# SCH_USB-HUB_2026-07-22.net
KiCad netlist of a schematic drawn in EasyEDA
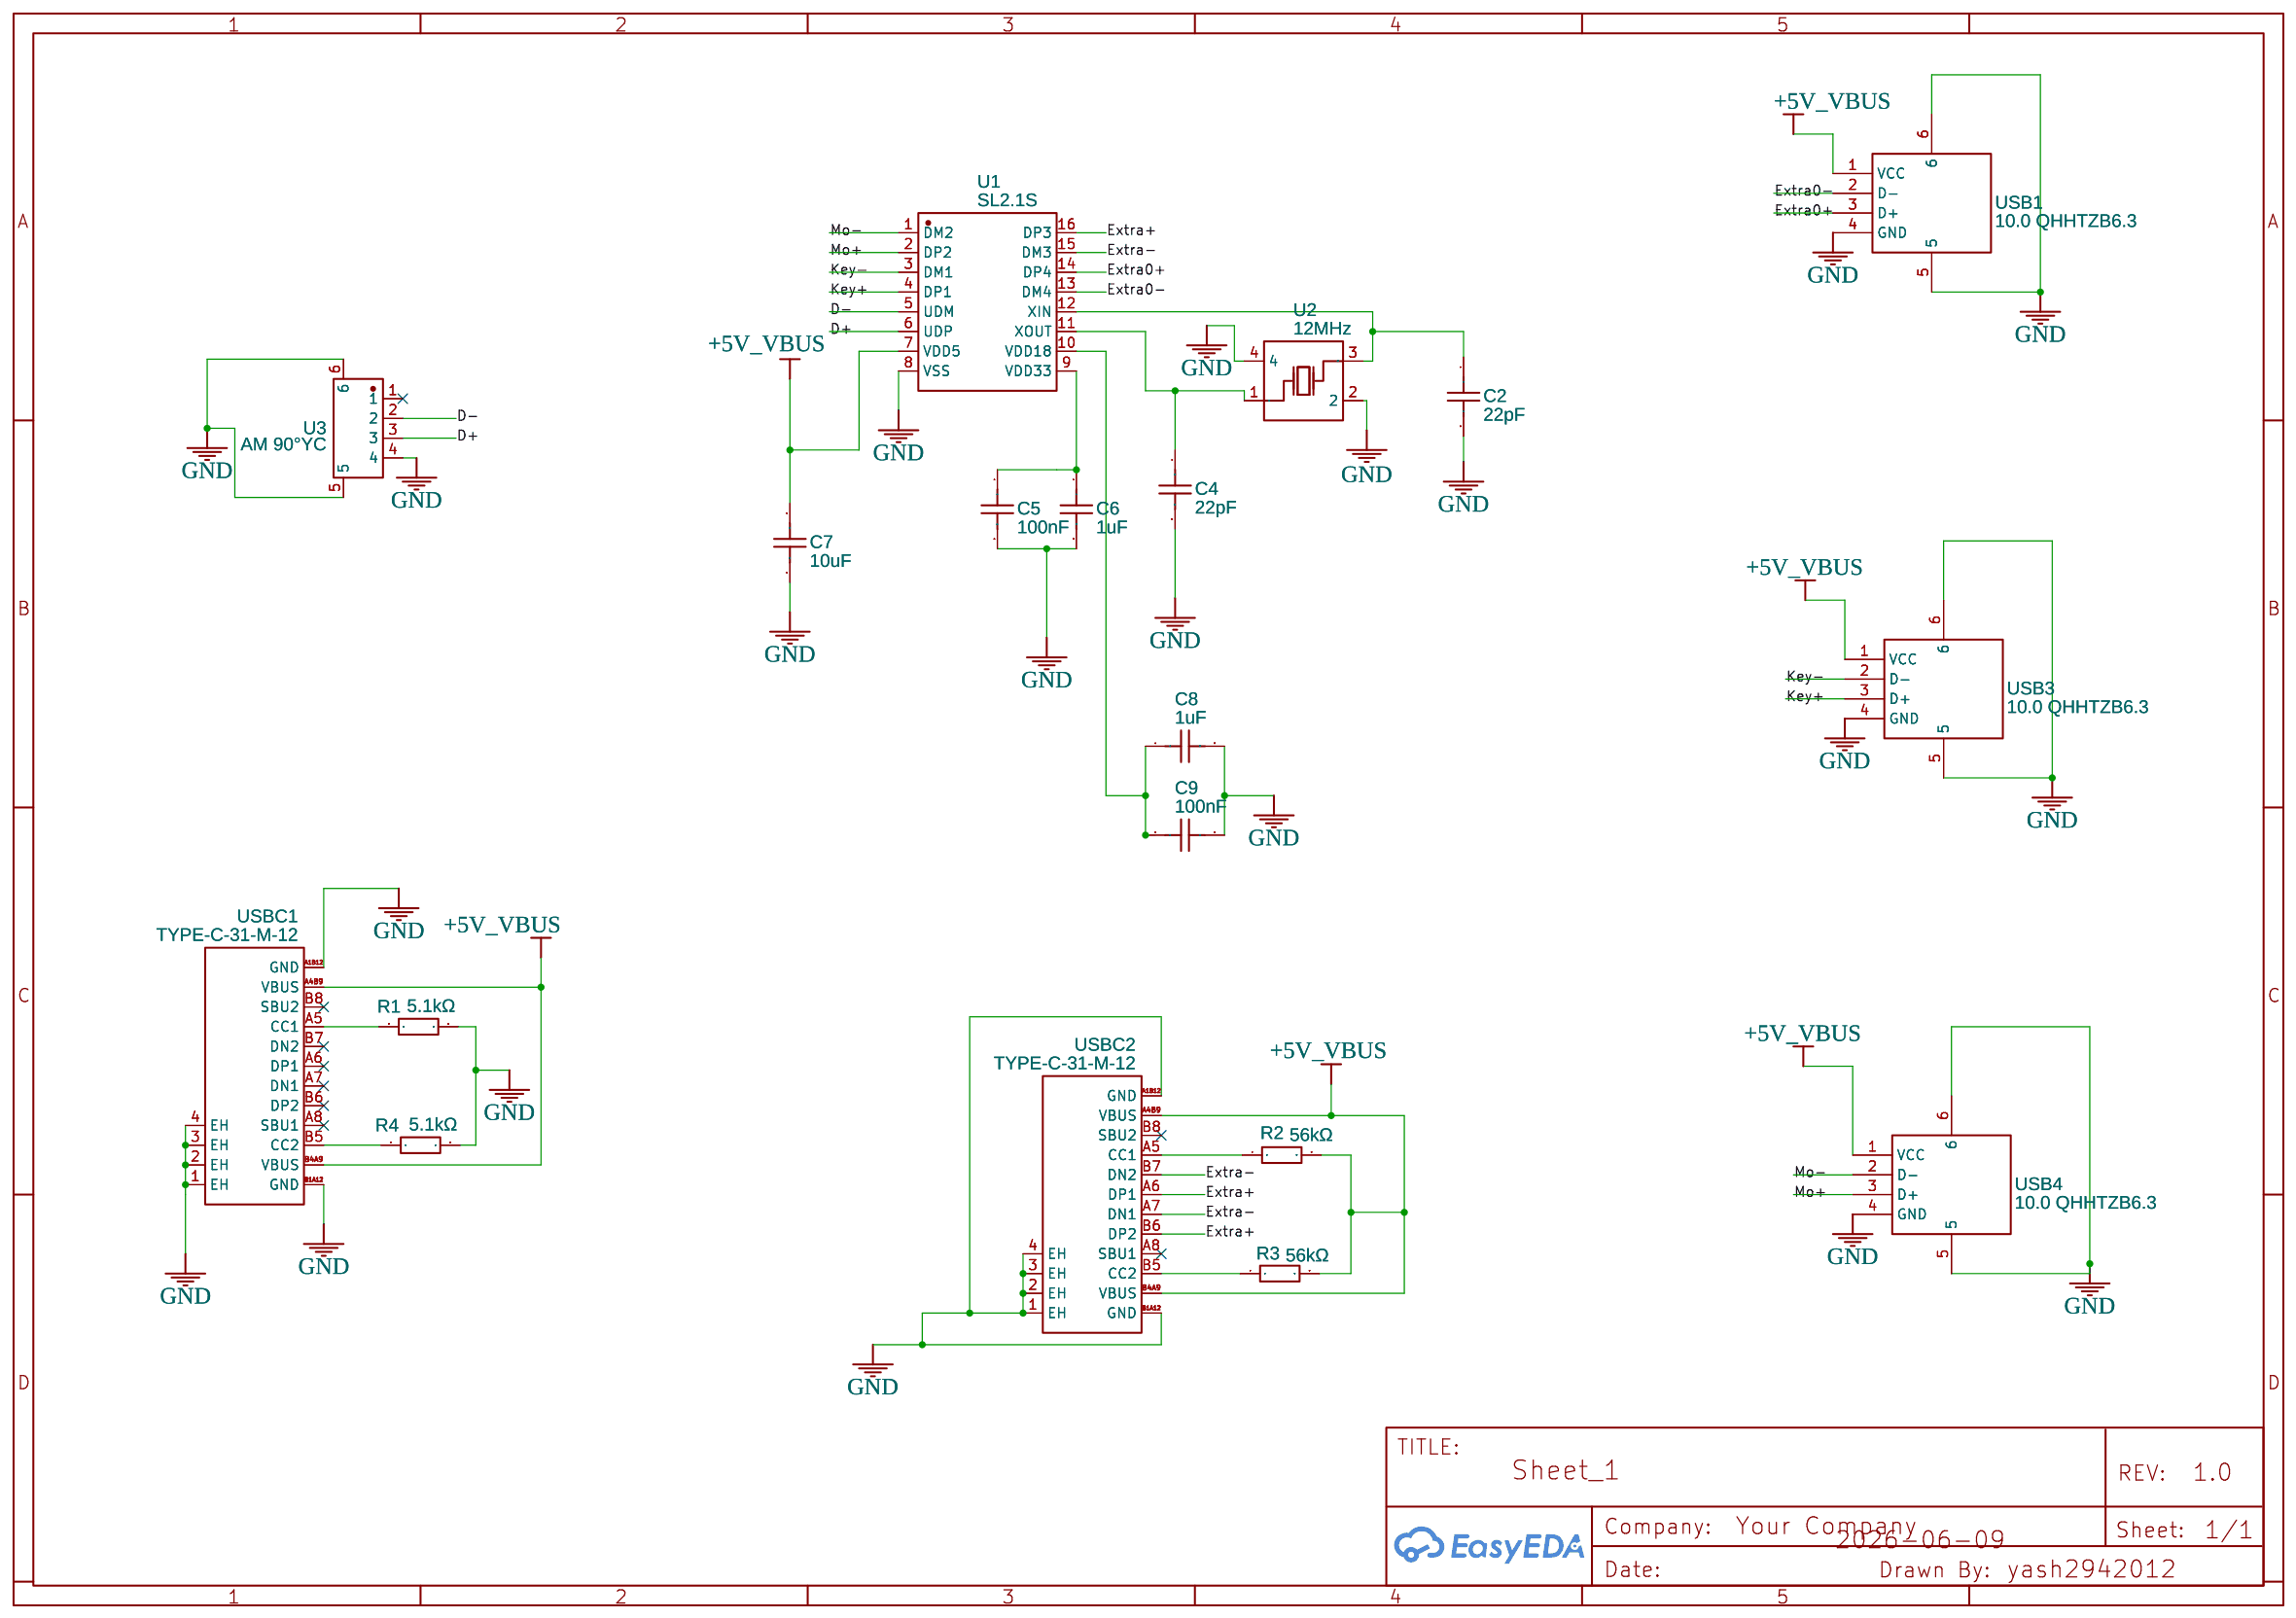
[diagram p0: schematic sheet]

(export (version "E")
  (design (tool "Eeschema 10.0.6"))
  (components
    (comp (ref "C2")
      (value "22pF")
      (fields
        (field (name "Manufacturer Part") "CC0603KRNPO9BN220")
        (field (name "Manufacturer") "YAGEO(国巨)")
      )
      (libsource (lib "") (part "CC0603KRNPO9BN220"))
    )
    (comp (ref "C4")
      (value "22pF")
      (fields
        (field (name "Manufacturer Part") "CC0603KRNPO9BN220")
        (field (name "Manufacturer") "YAGEO(国巨)")
      )
      (libsource (lib "") (part "CC0603KRNPO9BN220"))
    )
    (comp (ref "C5")
      (value "100nF")
      (fields
        (field (name "Manufacturer Part") "CL05B104KO5NNNC")
        (field (name "Manufacturer") "SAMSUNG(三星)")
      )
      (libsource (lib "") (part "CL05B104KO5NNNC"))
    )
    (comp (ref "C6")
      (value "1uF")
      (fields
        (field (name "Manufacturer Part") "CC0805KKX5R5BB105")
        (field (name "Manufacturer") "YAGEO(国巨)")
      )
      (libsource (lib "") (part "CC0805KKX5R5BB105_1"))
    )
    (comp (ref "C7")
      (value "10uF")
      (fields
        (field (name "Manufacturer Part") "CC0805KKX5R5BB106")
        (field (name "Manufacturer") "YAGEO(国巨)")
      )
      (libsource (lib "") (part "CC0805KKX5R5BB106"))
    )
    (comp (ref "C8")
      (value "1uF")
      (fields
        (field (name "Manufacturer Part") "CC0805KKX5R5BB105")
        (field (name "Manufacturer") "YAGEO(国巨)")
      )
      (libsource (lib "") (part "CC0805KKX5R5BB105"))
    )
    (comp (ref "C9")
      (value "100nF")
      (fields
        (field (name "Manufacturer Part") "CL05B104KO5NNNC")
        (field (name "Manufacturer") "SAMSUNG(三星)")
      )
      (libsource (lib "") (part "CL05B104KO5NNNC_1"))
    )
    (comp (ref "R1")
      (value "5.1kΩ")
      (fields
        (field (name "Manufacturer Part") "0402WGF5101TCE")
        (field (name "Manufacturer") "UNI-ROYAL(厚声)")
      )
      (libsource (lib "") (part "0402WGF5101TCE"))
    )
    (comp (ref "R2")
      (value "56kΩ")
      (fields
        (field (name "Manufacturer Part") "0402WGF5602TCE")
        (field (name "Manufacturer") "UNI-ROYAL(厚声)")
      )
      (libsource (lib "") (part "0402WGF5602TCE"))
    )
    (comp (ref "R3")
      (value "56kΩ")
      (fields
        (field (name "Manufacturer Part") "0402WGF5602TCE")
        (field (name "Manufacturer") "UNI-ROYAL(厚声)")
      )
      (libsource (lib "") (part "0402WGF5602TCE"))
    )
    (comp (ref "R4")
      (value "5.1kΩ")
      (fields
        (field (name "Manufacturer Part") "0402WGF5101TCE")
        (field (name "Manufacturer") "UNI-ROYAL(厚声)")
      )
      (libsource (lib "") (part "0402WGF5101TCE"))
    )
    (comp (ref "U1")
      (value "SL2.1S")
      (fields (field (name "Manufacturer Part") "SL2.1s") (field (name "Manufacturer") "CoreChips(和芯润德)"))
      (libsource (lib "") (part "SL2.1S"))
    )
    (comp (ref "U2")
      (value "12MHz")
      (fields
        (field (name "Manufacturer Part") "ABM10AIG-12.000MHZ-4Z-T3")
        (field (name "Manufacturer") "ABRACON")
      )
      (libsource (lib "") (part "ABM10AIG-12.000MHZ-4Z-T3"))
    )
    (comp (ref "U3")
      (value "AM 90°YC")
      (fields (field (name "Manufacturer Part") "AM 90 YC") (field (name "Manufacturer") "SHOU HAN(首韩)"))
      (libsource (lib "") (part "AM 90°YC"))
    )
    (comp (ref "USB1")
      (value "10.0 QHHTZB6.3")
      (fields (field (name "Manufacturer") "SHOU HAN(首韩)"))
      (libsource (lib "") (part "10.0 QHHTZB6.3"))
    )
    (comp (ref "USB3")
      (value "10.0 QHHTZB6.3")
      (fields (field (name "Manufacturer") "SHOU HAN(首韩)"))
      (libsource (lib "") (part "10.0 QHHTZB6.3"))
    )
    (comp (ref "USB4")
      (value "10.0 QHHTZB6.3")
      (fields (field (name "Manufacturer") "SHOU HAN(首韩)"))
      (libsource (lib "") (part "10.0 QHHTZB6.3"))
    )
    (comp (ref "USBC1")
      (value "TYPE-C-31-M-12")
      (fields (field (name "Manufacturer") "韩国韩荣"))
      (libsource (lib "") (part "TYPE-C-31-M-12"))
    )
    (comp (ref "USBC2")
      (value "TYPE-C-31-M-12")
      (fields (field (name "Manufacturer") "韩国韩荣"))
      (libsource (lib "") (part "TYPE-C-31-M-12"))
    )
  )
  (nets
    (net (code "1") (name "+5V_VBUS") (class "Default")
      (node (ref "C7") (pin "1") (pinfunction "1_1") (pintype "unspecified"))
      (node (ref "R2") (pin "2") (pinfunction "2_2") (pintype "input"))
      (node (ref "R3") (pin "2") (pinfunction "2_2") (pintype "input"))
      (node (ref "U1") (pin "7") (pinfunction "VDD5_7") (pintype "unspecified"))
      (node (ref "USB1") (pin "1") (pinfunction "VCC_1") (pintype "unspecified"))
      (node (ref "USB3") (pin "1") (pinfunction "VCC_1") (pintype "unspecified"))
      (node (ref "USB4") (pin "1") (pinfunction "VCC_1") (pintype "unspecified"))
      (node (ref "USBC1") (pin "A4B9") (pinfunction "VBUS_A4B9") (pintype "unspecified"))
      (node (ref "USBC1") (pin "B4A9") (pinfunction "VBUS_B4A9") (pintype "unspecified"))
      (node (ref "USBC2") (pin "A4B9") (pinfunction "VBUS_A4B9") (pintype "unspecified"))
      (node (ref "USBC2") (pin "B4A9") (pinfunction "VBUS_B4A9") (pintype "unspecified"))
    )
    (net (code "2") (name "/D+") (class "Default")
      (node (ref "U1") (pin "6") (pinfunction "UDP_6") (pintype "unspecified"))
      (node (ref "U3") (pin "3") (pinfunction "3_3") (pintype "unspecified"))
    )
    (net (code "3") (name "/D-") (class "Default")
      (node (ref "U1") (pin "5") (pinfunction "UDM_5") (pintype "unspecified"))
      (node (ref "U3") (pin "2") (pinfunction "2_2") (pintype "unspecified"))
    )
    (net (code "4") (name "/Extra+") (class "Default")
      (node (ref "U1") (pin "16") (pinfunction "DP3_16") (pintype "unspecified"))
      (node (ref "USBC2") (pin "A6") (pinfunction "DP1_A6") (pintype "unspecified"))
      (node (ref "USBC2") (pin "B6") (pinfunction "DP2_B6") (pintype "unspecified"))
    )
    (net (code "5") (name "/Extra-") (class "Default")
      (node (ref "U1") (pin "15") (pinfunction "DM3_15") (pintype "unspecified"))
      (node (ref "USBC2") (pin "A7") (pinfunction "DN1_A7") (pintype "unspecified"))
      (node (ref "USBC2") (pin "B7") (pinfunction "DN2_B7") (pintype "unspecified"))
    )
    (net (code "6") (name "/Extra0+") (class "Default")
      (node (ref "U1") (pin "14") (pinfunction "DP4_14") (pintype "unspecified"))
      (node (ref "USB1") (pin "3") (pinfunction "D+_3") (pintype "unspecified"))
    )
    (net (code "7") (name "/Extra0-") (class "Default")
      (node (ref "U1") (pin "13") (pinfunction "DM4_13") (pintype "unspecified"))
      (node (ref "USB1") (pin "2") (pinfunction "D-_2") (pintype "unspecified"))
    )
    (net (code "8") (name "/Key+") (class "Default")
      (node (ref "U1") (pin "4") (pinfunction "DP1_4") (pintype "unspecified"))
      (node (ref "USB3") (pin "3") (pinfunction "D+_3") (pintype "unspecified"))
    )
    (net (code "9") (name "/Key-") (class "Default")
      (node (ref "U1") (pin "3") (pinfunction "DM1_3") (pintype "unspecified"))
      (node (ref "USB3") (pin "2") (pinfunction "D-_2") (pintype "unspecified"))
    )
    (net (code "10") (name "/Mo+") (class "Default")
      (node (ref "U1") (pin "2") (pinfunction "DP2_2") (pintype "unspecified"))
      (node (ref "USB4") (pin "3") (pinfunction "D+_3") (pintype "unspecified"))
    )
    (net (code "11") (name "/Mo-") (class "Default")
      (node (ref "U1") (pin "1") (pinfunction "DM2_1") (pintype "unspecified"))
      (node (ref "USB4") (pin "2") (pinfunction "D-_2") (pintype "unspecified"))
    )
    (net (code "12") (name "GND") (class "Default")
      (node (ref "C2") (pin "2") (pinfunction "2_2") (pintype "unspecified"))
      (node (ref "C4") (pin "2") (pinfunction "2_2") (pintype "unspecified"))
      (node (ref "C5") (pin "2") (pinfunction "2_2") (pintype "unspecified"))
      (node (ref "C6") (pin "2") (pinfunction "2_2") (pintype "unspecified"))
      (node (ref "C7") (pin "2") (pinfunction "2_2") (pintype "unspecified"))
      (node (ref "C8") (pin "2") (pinfunction "2_2") (pintype "unspecified"))
      (node (ref "C9") (pin "2") (pinfunction "2_2") (pintype "unspecified"))
      (node (ref "R1") (pin "2") (pinfunction "2_2") (pintype "input"))
      (node (ref "R4") (pin "2") (pinfunction "2_2") (pintype "input"))
      (node (ref "U1") (pin "8") (pinfunction "VSS_8") (pintype "unspecified"))
      (node (ref "U2") (pin "2") (pinfunction "2_2") (pintype "unspecified"))
      (node (ref "U2") (pin "4") (pinfunction "4_4") (pintype "unspecified"))
      (node (ref "U3") (pin "4") (pinfunction "4_4") (pintype "unspecified"))
      (node (ref "U3") (pin "5") (pinfunction "5_5") (pintype "unspecified"))
      (node (ref "U3") (pin "6") (pinfunction "6_6") (pintype "unspecified"))
      (node (ref "USB1") (pin "4") (pinfunction "GND_4") (pintype "unspecified"))
      (node (ref "USB1") (pin "5") (pinfunction "5_5") (pintype "unspecified"))
      (node (ref "USB1") (pin "6") (pinfunction "6_6") (pintype "unspecified"))
      (node (ref "USB3") (pin "4") (pinfunction "GND_4") (pintype "unspecified"))
      (node (ref "USB3") (pin "5") (pinfunction "5_5") (pintype "unspecified"))
      (node (ref "USB3") (pin "6") (pinfunction "6_6") (pintype "unspecified"))
      (node (ref "USB4") (pin "4") (pinfunction "GND_4") (pintype "unspecified"))
      (node (ref "USB4") (pin "5") (pinfunction "5_5") (pintype "unspecified"))
      (node (ref "USB4") (pin "6") (pinfunction "6_6") (pintype "unspecified"))
      (node (ref "USBC1") (pin "1") (pinfunction "EH_1") (pintype "unspecified"))
      (node (ref "USBC1") (pin "2") (pinfunction "EH_2") (pintype "unspecified"))
      (node (ref "USBC1") (pin "3") (pinfunction "EH_3") (pintype "unspecified"))
      (node (ref "USBC1") (pin "4") (pinfunction "EH_4") (pintype "unspecified"))
      (node (ref "USBC1") (pin "A1B12") (pinfunction "GND_A1B12") (pintype "unspecified"))
      (node (ref "USBC1") (pin "B1A12") (pinfunction "GND_B1A12") (pintype "unspecified"))
      (node (ref "USBC2") (pin "1") (pinfunction "EH_1") (pintype "unspecified"))
      (node (ref "USBC2") (pin "2") (pinfunction "EH_2") (pintype "unspecified"))
      (node (ref "USBC2") (pin "3") (pinfunction "EH_3") (pintype "unspecified"))
      (node (ref "USBC2") (pin "4") (pinfunction "EH_4") (pintype "unspecified"))
      (node (ref "USBC2") (pin "A1B12") (pinfunction "GND_A1B12") (pintype "unspecified"))
      (node (ref "USBC2") (pin "B1A12") (pinfunction "GND_B1A12") (pintype "unspecified"))
    )
    (net (code "13") (name "Net-(U1-VDD18)") (class "Default")
      (node (ref "C8") (pin "1") (pinfunction "1_1") (pintype "unspecified"))
      (node (ref "C9") (pin "1") (pinfunction "1_1") (pintype "unspecified"))
      (node (ref "U1") (pin "10") (pinfunction "VDD18_10") (pintype "unspecified"))
    )
    (net (code "14") (name "Net-(U1-VDD33)") (class "Default")
      (node (ref "C5") (pin "1") (pinfunction "1_1") (pintype "unspecified"))
      (node (ref "C6") (pin "1") (pinfunction "1_1") (pintype "unspecified"))
      (node (ref "U1") (pin "9") (pinfunction "VDD33_9") (pintype "unspecified"))
    )
    (net (code "15") (name "Net-(U1-XIN)") (class "Default")
      (node (ref "C2") (pin "1") (pinfunction "1_1") (pintype "unspecified"))
      (node (ref "U1") (pin "12") (pinfunction "XIN_12") (pintype "unspecified"))
      (node (ref "U2") (pin "3") (pinfunction "OSC2_3") (pintype "unspecified"))
    )
    (net (code "16") (name "Net-(U1-XOUT)") (class "Default")
      (node (ref "C4") (pin "1") (pinfunction "1_1") (pintype "unspecified"))
      (node (ref "U1") (pin "11") (pinfunction "XOUT_11") (pintype "unspecified"))
      (node (ref "U2") (pin "1") (pinfunction "OSC1_1") (pintype "unspecified"))
    )
    (net (code "17") (name "Net-(USBC1-CC1)") (class "Default")
      (node (ref "R1") (pin "1") (pinfunction "1_1") (pintype "input"))
      (node (ref "USBC1") (pin "A5") (pinfunction "CC1_A5") (pintype "unspecified"))
    )
    (net (code "18") (name "Net-(USBC1-CC2)") (class "Default")
      (node (ref "R4") (pin "1") (pinfunction "1_1") (pintype "input"))
      (node (ref "USBC1") (pin "B5") (pinfunction "CC2_B5") (pintype "unspecified"))
    )
    (net (code "19") (name "Net-(USBC2-CC1)") (class "Default")
      (node (ref "R2") (pin "1") (pinfunction "1_1") (pintype "input"))
      (node (ref "USBC2") (pin "A5") (pinfunction "CC1_A5") (pintype "unspecified"))
    )
    (net (code "20") (name "Net-(USBC2-CC2)") (class "Default")
      (node (ref "R3") (pin "1") (pinfunction "1_1") (pintype "input"))
      (node (ref "USBC2") (pin "B5") (pinfunction "CC2_B5") (pintype "unspecified"))
    )
    (net (code "21") (name "unconnected-(U3-Pad1)") (class "Default")
      (node (ref "U3") (pin "1") (pinfunction "1_1") (pintype "unspecified+no_connect"))
    )
    (net (code "22") (name "unconnected-(USBC1-DN1-PadA7)") (class "Default")
      (node (ref "USBC1") (pin "A7") (pinfunction "DN1_A7") (pintype "unspecified+no_connect"))
    )
    (net (code "23") (name "unconnected-(USBC1-DN2-PadB7)") (class "Default")
      (node (ref "USBC1") (pin "B7") (pinfunction "DN2_B7") (pintype "unspecified+no_connect"))
    )
    (net (code "24") (name "unconnected-(USBC1-DP1-PadA6)") (class "Default")
      (node (ref "USBC1") (pin "A6") (pinfunction "DP1_A6") (pintype "unspecified+no_connect"))
    )
    (net (code "25") (name "unconnected-(USBC1-DP2-PadB6)") (class "Default")
      (node (ref "USBC1") (pin "B6") (pinfunction "DP2_B6") (pintype "unspecified+no_connect"))
    )
    (net (code "26") (name "unconnected-(USBC1-SBU1-PadA8)") (class "Default")
      (node (ref "USBC1") (pin "A8") (pinfunction "SBU1_A8") (pintype "unspecified+no_connect"))
    )
    (net (code "27") (name "unconnected-(USBC1-SBU2-PadB8)") (class "Default")
      (node (ref "USBC1") (pin "B8") (pinfunction "SBU2_B8") (pintype "unspecified+no_connect"))
    )
    (net (code "28") (name "unconnected-(USBC2-SBU1-PadA8)") (class "Default")
      (node (ref "USBC2") (pin "A8") (pinfunction "SBU1_A8") (pintype "unspecified+no_connect"))
    )
    (net (code "29") (name "unconnected-(USBC2-SBU2-PadB8)") (class "Default")
      (node (ref "USBC2") (pin "B8") (pinfunction "SBU2_B8") (pintype "unspecified+no_connect"))
    )
  )
)
